# ETH.net
KiCad netlist of a schematic drawn in Altium Designer
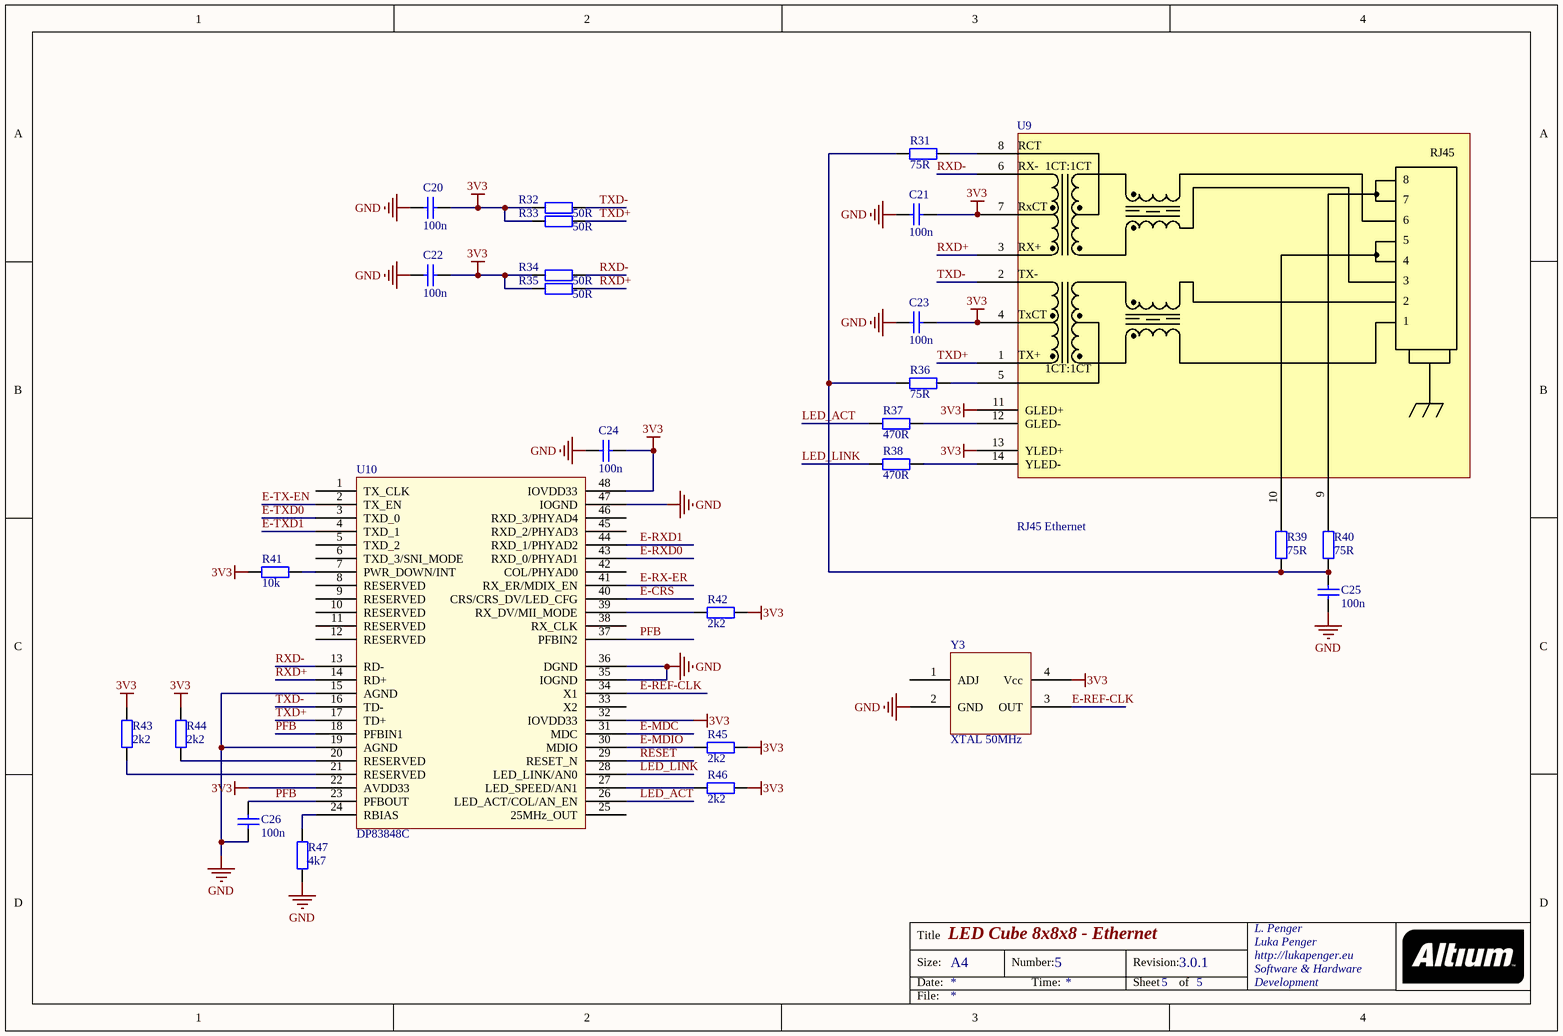
[diagram p0: ETH.SchDoc]

(export (version "E")
  (design (tool "Eeschema 10.0.6"))
  (components
    (comp (ref "C20")
      (value "100n")
      (footprint "1608[0603]")
      (description "Capacitor")
      (fields (field (name "PUBLISHER") "Altium Limited"))
      (libsource (lib "Miscellaneous Devices") (part "Cap"))
    )
    (comp (ref "C21")
      (value "100n")
      (footprint "1608[0603]")
      (description "Capacitor")
      (fields (field (name "PUBLISHER") "Altium Limited"))
      (libsource (lib "Miscellaneous Devices") (part "Cap"))
    )
    (comp (ref "C22")
      (value "100n")
      (footprint "1608[0603]")
      (description "Capacitor")
      (fields (field (name "PUBLISHER") "Altium Limited"))
      (libsource (lib "Miscellaneous Devices") (part "Cap"))
    )
    (comp (ref "C23")
      (value "100n")
      (footprint "1608[0603]")
      (description "Capacitor")
      (fields (field (name "PUBLISHER") "Altium Limited"))
      (libsource (lib "Miscellaneous Devices") (part "Cap"))
    )
    (comp (ref "C24")
      (value "100n")
      (footprint "1608[0603]")
      (description "Capacitor")
      (fields (field (name "PUBLISHER") "Altium Limited"))
      (libsource (lib "Miscellaneous Devices") (part "Cap"))
    )
    (comp (ref "C25")
      (value "100n")
      (footprint "1608[0603]")
      (description "Capacitor")
      (fields (field (name "PUBLISHER") "Altium Limited"))
      (libsource (lib "Miscellaneous Devices") (part "Cap"))
    )
    (comp (ref "C26")
      (value "100n")
      (footprint "6-0805_L")
      (description "Capacitor")
      (fields (field (name "PUBLISHER") "Altium Limited"))
      (libsource (lib "Miscellaneous Devices") (part "Cap"))
    )
    (comp (ref "R31")
      (value "75R")
      (footprint "1608[0603]")
      (description "Resistor")
      (fields (field (name "PUBLISHER") "Altium Limited"))
      (libsource (lib "Miscellaneous Devices") (part "Res2"))
    )
    (comp (ref "R32")
      (value "50R")
      (footprint "1608[0603]")
      (description "Resistor")
      (fields (field (name "PUBLISHER") "Altium Limited"))
      (libsource (lib "Miscellaneous Devices") (part "Res2"))
    )
    (comp (ref "R33")
      (value "50R")
      (footprint "1608[0603]")
      (description "Resistor")
      (fields (field (name "PUBLISHER") "Altium Limited"))
      (libsource (lib "Miscellaneous Devices") (part "Res2"))
    )
    (comp (ref "R34")
      (value "50R")
      (footprint "1608[0603]")
      (description "Resistor")
      (fields (field (name "PUBLISHER") "Altium Limited"))
      (libsource (lib "Miscellaneous Devices") (part "Res2"))
    )
    (comp (ref "R35")
      (value "50R")
      (footprint "1608[0603]")
      (description "Resistor")
      (fields (field (name "PUBLISHER") "Altium Limited"))
      (libsource (lib "Miscellaneous Devices") (part "Res2"))
    )
    (comp (ref "R36")
      (value "75R")
      (footprint "1608[0603]")
      (description "Resistor")
      (fields (field (name "PUBLISHER") "Altium Limited"))
      (libsource (lib "Miscellaneous Devices") (part "Res2"))
    )
    (comp (ref "R37")
      (value "470R")
      (footprint "1608[0603]")
      (description "Resistor")
      (fields (field (name "PUBLISHER") "Altium Limited"))
      (libsource (lib "Miscellaneous Devices") (part "Res2"))
    )
    (comp (ref "R38")
      (value "470R")
      (footprint "1608[0603]")
      (description "Resistor")
      (fields (field (name "PUBLISHER") "Altium Limited"))
      (libsource (lib "Miscellaneous Devices") (part "Res2"))
    )
    (comp (ref "R39")
      (value "75R")
      (footprint "1608[0603]")
      (description "Resistor")
      (fields (field (name "PUBLISHER") "Altium Limited"))
      (libsource (lib "") (part "Res2_1"))
    )
    (comp (ref "R40")
      (value "75R")
      (footprint "1608[0603]")
      (description "Resistor")
      (fields (field (name "PUBLISHER") "Altium Limited"))
      (libsource (lib "") (part "Res2_1"))
    )
    (comp (ref "R41")
      (value "10k")
      (footprint "1608[0603]")
      (description "Resistor")
      (fields (field (name "PUBLISHER") "Altium Limited"))
      (libsource (lib "Miscellaneous Devices") (part "Res2"))
    )
    (comp (ref "R42")
      (value "2k2")
      (footprint "1608[0603]")
      (description "Resistor")
      (fields (field (name "PUBLISHER") "Altium Limited"))
      (libsource (lib "Miscellaneous Devices") (part "Res2"))
    )
    (comp (ref "R43")
      (value "2k2")
      (footprint "1608[0603]")
      (description "Resistor")
      (fields (field (name "PUBLISHER") "Altium Limited"))
      (libsource (lib "") (part "Res2_2"))
    )
    (comp (ref "R44")
      (value "2k2")
      (footprint "1608[0603]")
      (description "Resistor")
      (fields (field (name "PUBLISHER") "Altium Limited"))
      (libsource (lib "") (part "Res2_1"))
    )
    (comp (ref "R45")
      (value "2k2")
      (footprint "1608[0603]")
      (description "Resistor")
      (fields (field (name "PUBLISHER") "Altium Limited"))
      (libsource (lib "Miscellaneous Devices") (part "Res2"))
    )
    (comp (ref "R46")
      (value "2k2")
      (footprint "1608[0603]")
      (description "Resistor")
      (fields (field (name "PUBLISHER") "Altium Limited"))
      (libsource (lib "Miscellaneous Devices") (part "Res2"))
    )
    (comp (ref "R47")
      (value "4k7")
      (footprint "1608[0603]")
      (description "Resistor")
      (fields (field (name "PUBLISHER") "Altium Limited"))
      (libsource (lib "") (part "Res2_2"))
    )
    (comp (ref "U9")
      (value "RJ45 Ethernet")
      (footprint "RJ45 Ethernet connector")
      (description "Ethernet Connector")
      (libsource (lib "LP_Lib") (part "RJ45 Ethernet"))
    )
    (comp (ref "U10")
      (value "DP83848C")
      (footprint "DP83848C")
      (description "Ethernet PHY")
      (libsource (lib "LP_Lib") (part "DP83848C"))
    )
    (comp (ref "Y3")
      (value "XTAL 50MHz")
      (footprint "XTAL ACT9200")
      (libsource (lib "LP_Lib") (part "XTAL ACT9200"))
    )
  )
  (nets
    (net (code "1") (name "/E-CRS") (class "Default")
      (node (ref "U10") (pin "40") (pinfunction "CRS/CRS_DV/LED_CFG_40") (pintype "passive"))
    )
    (net (code "2") (name "/E-MDC") (class "Default")
      (node (ref "U10") (pin "31") (pinfunction "MDC_31") (pintype "passive"))
    )
    (net (code "3") (name "/E-MDIO") (class "Default")
      (node (ref "R45") (pin "2") (pinfunction "2_2") (pintype "passive"))
      (node (ref "U10") (pin "30") (pinfunction "MDIO_30") (pintype "passive"))
    )
    (net (code "4") (name "/E-REF-CLK") (class "Default")
      (node (ref "U10") (pin "34") (pinfunction "X1_34") (pintype "passive"))
      (node (ref "Y3") (pin "3") (pinfunction "OUT_3") (pintype "passive"))
    )
    (net (code "5") (name "/E-RX-ER") (class "Default")
      (node (ref "U10") (pin "41") (pinfunction "RX_ER/MDIX_EN_41") (pintype "passive"))
    )
    (net (code "6") (name "/E-RXD0") (class "Default")
      (node (ref "U10") (pin "43") (pinfunction "RXD_0/PHYAD1_43") (pintype "passive"))
    )
    (net (code "7") (name "/E-RXD1") (class "Default")
      (node (ref "U10") (pin "44") (pinfunction "RXD_1/PHYAD2_44") (pintype "passive"))
    )
    (net (code "8") (name "/E-TX-EN") (class "Default")
      (node (ref "U10") (pin "2") (pinfunction "TX_EN_2") (pintype "passive"))
    )
    (net (code "9") (name "/E-TXD0") (class "Default")
      (node (ref "U10") (pin "3") (pinfunction "TXD_0_3") (pintype "passive"))
    )
    (net (code "10") (name "/E-TXD1") (class "Default")
      (node (ref "U10") (pin "4") (pinfunction "TXD_1_4") (pintype "passive"))
    )
    (net (code "11") (name "/LED_ACT") (class "Default")
      (node (ref "R37") (pin "2") (pinfunction "2_2") (pintype "passive"))
      (node (ref "U10") (pin "26") (pinfunction "LED_ACT/COL/AN_EN_26") (pintype "passive"))
    )
    (net (code "12") (name "/LED_LINK") (class "Default")
      (node (ref "R38") (pin "2") (pinfunction "2_2") (pintype "passive"))
      (node (ref "U10") (pin "28") (pinfunction "LED_LINK/AN0_28") (pintype "passive"))
    )
    (net (code "13") (name "/PFB") (class "Default")
      (node (ref "C26") (pin "1") (pinfunction "1_1") (pintype "passive"))
      (node (ref "U10") (pin "18") (pinfunction "PFBIN1_18") (pintype "passive"))
      (node (ref "U10") (pin "23") (pinfunction "PFBOUT_23") (pintype "passive"))
      (node (ref "U10") (pin "37") (pinfunction "PFBIN2_37") (pintype "passive"))
    )
    (net (code "14") (name "/RESET") (class "Default")
      (node (ref "U10") (pin "29") (pinfunction "RESET_N_29") (pintype "passive"))
    )
    (net (code "15") (name "/RXD+") (class "Default")
      (node (ref "R35") (pin "1") (pinfunction "1_1") (pintype "passive"))
      (node (ref "U10") (pin "14") (pinfunction "RD+_14") (pintype "passive"))
      (node (ref "U9") (pin "3") (pintype "passive"))
    )
    (net (code "16") (name "/RXD-") (class "Default")
      (node (ref "R34") (pin "1") (pinfunction "1_1") (pintype "passive"))
      (node (ref "U10") (pin "13") (pinfunction "RD-_13") (pintype "passive"))
      (node (ref "U9") (pin "6") (pintype "passive"))
    )
    (net (code "17") (name "/TXD+") (class "Default")
      (node (ref "R33") (pin "1") (pinfunction "1_1") (pintype "passive"))
      (node (ref "U10") (pin "17") (pinfunction "TD+_17") (pintype "passive"))
      (node (ref "U9") (pin "1") (pintype "passive"))
    )
    (net (code "18") (name "/TXD-") (class "Default")
      (node (ref "R32") (pin "1") (pinfunction "1_1") (pintype "passive"))
      (node (ref "U10") (pin "16") (pinfunction "TD-_16") (pintype "passive"))
      (node (ref "U9") (pin "2") (pintype "passive"))
    )
    (net (code "19") (name "3V3") (class "Default")
      (node (ref "C20") (pin "2") (pinfunction "2_2") (pintype "passive"))
      (node (ref "C21") (pin "2") (pinfunction "2_2") (pintype "passive"))
      (node (ref "C22") (pin "2") (pinfunction "2_2") (pintype "passive"))
      (node (ref "C23") (pin "2") (pinfunction "2_2") (pintype "passive"))
      (node (ref "C24") (pin "2") (pinfunction "2_2") (pintype "passive"))
      (node (ref "R32") (pin "2") (pinfunction "2_2") (pintype "passive"))
      (node (ref "R33") (pin "2") (pinfunction "2_2") (pintype "passive"))
      (node (ref "R34") (pin "2") (pinfunction "2_2") (pintype "passive"))
      (node (ref "R35") (pin "2") (pinfunction "2_2") (pintype "passive"))
      (node (ref "R41") (pin "2") (pinfunction "2_2") (pintype "passive"))
      (node (ref "R42") (pin "1") (pinfunction "1_1") (pintype "passive"))
      (node (ref "R43") (pin "1") (pinfunction "1_1") (pintype "passive"))
      (node (ref "R44") (pin "2") (pinfunction "2_2") (pintype "passive"))
      (node (ref "R45") (pin "1") (pinfunction "1_1") (pintype "passive"))
      (node (ref "R46") (pin "1") (pinfunction "1_1") (pintype "passive"))
      (node (ref "U10") (pin "22") (pinfunction "AVDD33_22") (pintype "passive"))
      (node (ref "U10") (pin "32") (pinfunction "IOVDD33_32") (pintype "passive"))
      (node (ref "U10") (pin "48") (pinfunction "IOVDD33_48") (pintype "passive"))
      (node (ref "U9") (pin "11") (pinfunction "GLED+_11") (pintype "passive"))
      (node (ref "U9") (pin "13") (pinfunction "YLED+_13") (pintype "passive"))
      (node (ref "U9") (pin "4") (pintype "passive"))
      (node (ref "U9") (pin "7") (pintype "passive"))
      (node (ref "Y3") (pin "4") (pinfunction "Vcc_4") (pintype "passive"))
    )
    (net (code "20") (name "GND") (class "Default")
      (node (ref "C20") (pin "1") (pinfunction "1_1") (pintype "passive"))
      (node (ref "C21") (pin "1") (pinfunction "1_1") (pintype "passive"))
      (node (ref "C22") (pin "1") (pinfunction "1_1") (pintype "passive"))
      (node (ref "C23") (pin "1") (pinfunction "1_1") (pintype "passive"))
      (node (ref "C24") (pin "1") (pinfunction "1_1") (pintype "passive"))
      (node (ref "C25") (pin "2") (pinfunction "2_2") (pintype "passive"))
      (node (ref "C26") (pin "2") (pinfunction "2_2") (pintype "passive"))
      (node (ref "R47") (pin "2") (pinfunction "2_2") (pintype "passive"))
      (node (ref "U10") (pin "15") (pinfunction "AGND_15") (pintype "passive"))
      (node (ref "U10") (pin "19") (pinfunction "AGND_19") (pintype "passive"))
      (node (ref "U10") (pin "35") (pinfunction "IOGND_35") (pintype "passive"))
      (node (ref "U10") (pin "36") (pinfunction "DGND_36") (pintype "passive"))
      (node (ref "U10") (pin "47") (pinfunction "IOGND_47") (pintype "passive"))
      (node (ref "Y3") (pin "2") (pinfunction "GND_2") (pintype "passive"))
    )
    (net (code "21") (name "Net-(C25-Pad1)") (class "Default")
      (node (ref "C25") (pin "1") (pinfunction "1_1") (pintype "passive"))
      (node (ref "R31") (pin "2") (pinfunction "2_2") (pintype "passive"))
      (node (ref "R36") (pin "2") (pinfunction "2_2") (pintype "passive"))
      (node (ref "R39") (pin "1") (pinfunction "1_1") (pintype "passive"))
      (node (ref "R40") (pin "1") (pinfunction "1_1") (pintype "passive"))
    )
    (net (code "22") (name "Net-(R31-Pad1)") (class "Default")
      (node (ref "R31") (pin "1") (pinfunction "1_1") (pintype "passive"))
      (node (ref "U9") (pin "8") (pintype "passive"))
    )
    (net (code "23") (name "Net-(R36-Pad1)") (class "Default")
      (node (ref "R36") (pin "1") (pinfunction "1_1") (pintype "passive"))
      (node (ref "U9") (pin "5") (pintype "passive"))
    )
    (net (code "24") (name "Net-(R39-Pad2)") (class "Default")
      (node (ref "R39") (pin "2") (pinfunction "2_2") (pintype "passive"))
      (node (ref "U9") (pin "10") (pintype "passive"))
    )
    (net (code "25") (name "Net-(R40-Pad2)") (class "Default")
      (node (ref "R40") (pin "2") (pinfunction "2_2") (pintype "passive"))
      (node (ref "U9") (pin "9") (pintype "passive"))
    )
    (net (code "26") (name "Net-(R43-Pad2)") (class "Default")
      (node (ref "R43") (pin "2") (pinfunction "2_2") (pintype "passive"))
      (node (ref "U10") (pin "21") (pinfunction "RESERVED_21") (pintype "passive"))
    )
    (net (code "27") (name "Net-(R44-Pad1)") (class "Default")
      (node (ref "R44") (pin "1") (pinfunction "1_1") (pintype "passive"))
      (node (ref "U10") (pin "20") (pinfunction "RESERVED_20") (pintype "passive"))
    )
    (net (code "28") (name "Net-(U9-GLED-)") (class "Default")
      (node (ref "R37") (pin "1") (pinfunction "1_1") (pintype "passive"))
      (node (ref "U9") (pin "12") (pinfunction "GLED-_12") (pintype "passive"))
    )
    (net (code "29") (name "Net-(U9-YLED-)") (class "Default")
      (node (ref "R38") (pin "1") (pinfunction "1_1") (pintype "passive"))
      (node (ref "U9") (pin "14") (pinfunction "YLED-_14") (pintype "passive"))
    )
    (net (code "30") (name "Net-(U10-LED_SPEED{slash}AN1)") (class "Default")
      (node (ref "R46") (pin "2") (pinfunction "2_2") (pintype "passive"))
      (node (ref "U10") (pin "27") (pinfunction "LED_SPEED/AN1_27") (pintype "passive"))
    )
    (net (code "31") (name "Net-(U10-PWR_DOWN{slash}INT)") (class "Default")
      (node (ref "R41") (pin "1") (pinfunction "1_1") (pintype "passive"))
      (node (ref "U10") (pin "7") (pinfunction "PWR_DOWN/INT_7") (pintype "passive"))
    )
    (net (code "32") (name "Net-(U10-RBIAS)") (class "Default")
      (node (ref "R47") (pin "1") (pinfunction "1_1") (pintype "passive"))
      (node (ref "U10") (pin "24") (pinfunction "RBIAS_24") (pintype "passive"))
    )
    (net (code "33") (name "Net-(U10-RX_DV{slash}MII_MODE)") (class "Default")
      (node (ref "R42") (pin "2") (pinfunction "2_2") (pintype "passive"))
      (node (ref "U10") (pin "39") (pinfunction "RX_DV/MII_MODE_39") (pintype "passive"))
    )
    (net (code "34") (name "unconnected-(U10-25MHz_OUT-Pad25)") (class "Default")
      (node (ref "U10") (pin "25") (pinfunction "25MHz_OUT_25") (pintype "passive"))
    )
    (net (code "35") (name "unconnected-(U10-COL{slash}PHYAD0-Pad42)") (class "Default")
      (node (ref "U10") (pin "42") (pinfunction "COL/PHYAD0_42") (pintype "passive"))
    )
    (net (code "36") (name "unconnected-(U10-RESERVED-Pad8)") (class "Default")
      (node (ref "U10") (pin "8") (pinfunction "RESERVED_8") (pintype "passive"))
    )
    (net (code "37") (name "unconnected-(U10-RESERVED-Pad9)") (class "Default")
      (node (ref "U10") (pin "9") (pinfunction "RESERVED_9") (pintype "passive"))
    )
    (net (code "38") (name "unconnected-(U10-RESERVED-Pad10)") (class "Default")
      (node (ref "U10") (pin "10") (pinfunction "RESERVED_10") (pintype "passive"))
    )
    (net (code "39") (name "unconnected-(U10-RESERVED-Pad11)") (class "Default")
      (node (ref "U10") (pin "11") (pinfunction "RESERVED_11") (pintype "passive"))
    )
    (net (code "40") (name "unconnected-(U10-RESERVED-Pad12)") (class "Default")
      (node (ref "U10") (pin "12") (pinfunction "RESERVED_12") (pintype "passive"))
    )
    (net (code "41") (name "unconnected-(U10-RXD_2{slash}PHYAD3-Pad45)") (class "Default")
      (node (ref "U10") (pin "45") (pinfunction "RXD_2/PHYAD3_45") (pintype "passive"))
    )
    (net (code "42") (name "unconnected-(U10-RXD_3{slash}PHYAD4-Pad46)") (class "Default")
      (node (ref "U10") (pin "46") (pinfunction "RXD_3/PHYAD4_46") (pintype "passive"))
    )
    (net (code "43") (name "unconnected-(U10-RX_CLK-Pad38)") (class "Default")
      (node (ref "U10") (pin "38") (pinfunction "RX_CLK_38") (pintype "passive"))
    )
    (net (code "44") (name "unconnected-(U10-TXD_2-Pad5)") (class "Default")
      (node (ref "U10") (pin "5") (pinfunction "TXD_2_5") (pintype "passive"))
    )
    (net (code "45") (name "unconnected-(U10-TXD_3{slash}SNI_MODE-Pad6)") (class "Default")
      (node (ref "U10") (pin "6") (pinfunction "TXD_3/SNI_MODE_6") (pintype "passive"))
    )
    (net (code "46") (name "unconnected-(U10-TX_CLK-Pad1)") (class "Default")
      (node (ref "U10") (pin "1") (pinfunction "TX_CLK_1") (pintype "passive"))
    )
    (net (code "47") (name "unconnected-(U10-X2-Pad33)") (class "Default")
      (node (ref "U10") (pin "33") (pinfunction "X2_33") (pintype "passive"))
    )
    (net (code "48") (name "unconnected-(Y3-ADJ-Pad1)") (class "Default")
      (node (ref "Y3") (pin "1") (pinfunction "ADJ_1") (pintype "passive"))
    )
  )
)
